# PWR.net
KiCad netlist of a schematic drawn in Altium Designer
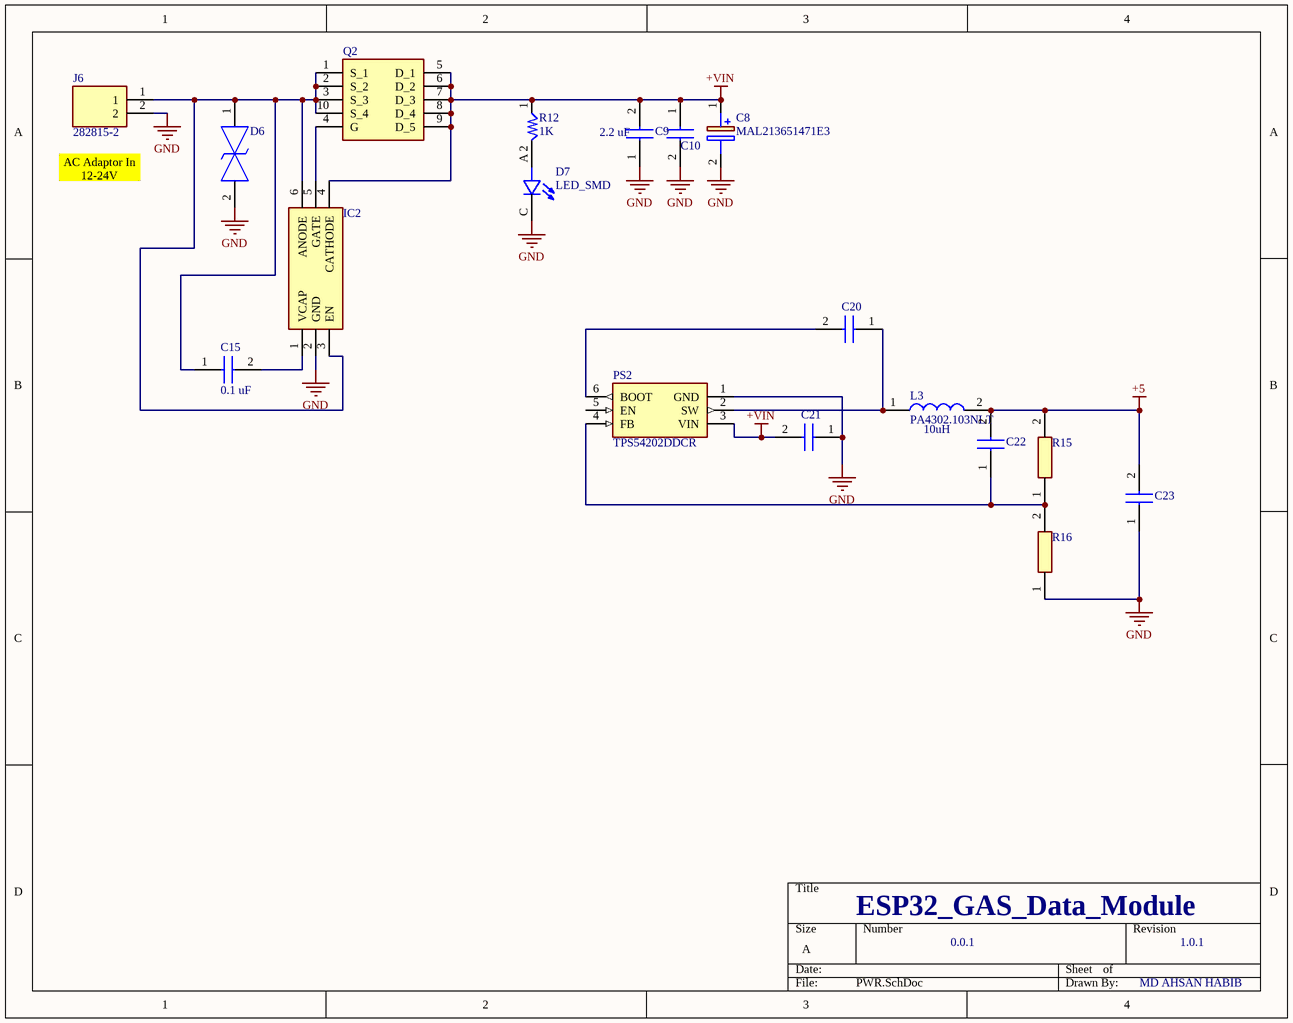
[diagram p0: PWR.SchDoc]

(export (version "E")
  (design (tool "Eeschema 10.0.6"))
  (components
    (comp (ref "C8")
      (value "MAL213651471E3")
      (footprint "CAPPRD500W60D1300H2700")
      (description "Capacitor Polarised")
      (fields (field (name "MOUSER PART NUMBER") "594-2222-136-51471"))
      (libsource (lib "Valve_Controller_Lib") (part "MAL213651471E3"))
    )
    (comp (ref "C9")
      (value "2.2 uF")
      (footprint "CAP0603")
      (description "Capacitor")
      (fields
        (field (name "MANUFACTURER_PART_NUMBER") "CC0603KRX7R9BB104")
        (field (name "MOUSER PART NUMBER") "603-CC603KRX7R9BB104")
      )
      (libsource (lib "Valve_Controller_Lib") (part "CC0603KRX7R9BB104"))
    )
    (comp (ref "C10")
      (value "C5750X5R1H106K230KA")
      (footprint "C5750_Commercial")
      (description "Capacitor")
      (fields (field (name "MOUSER PART NUMBER") "810-C5750X5R1H106K"))
      (libsource (lib "Valve_Controller_Lib") (part "C5750X5R1H106K230KA"))
    )
    (comp (ref "C15")
      (value "0.1 uF")
      (footprint "CAP0603")
      (description "Capacitor")
      (fields
        (field (name "MANUFACTURER_PART_NUMBER") "CC0603KRX7R9BB104")
        (field (name "MOUSER PART NUMBER") "603-CC603KRX7R9BB104")
      )
      (libsource (lib "Valve_Controller_Lib") (part "CC0603KRX7R9BB104"))
    )
    (comp (ref "C20")
      (value "C0805C104M5RAC-TU")
      (footprint "CAPC2012X88N")
      (description "Capacitor")
      (libsource (lib "Valve_Controller_Lib") (part "C0805C104M5RAC-TU"))
    )
    (comp (ref "C21")
      (value "C5750X5R1H106K230KA")
      (footprint "CAP0603")
      (description "Capacitor")
      (fields (field (name "MOUSER PART NUMBER") "810-C5750X5R1H106K"))
      (libsource (lib "Valve_Controller_Lib") (part "C5750X5R1H106K230KA"))
    )
    (comp (ref "C22")
      (value "CGA1A2C0G1E820J030BA")
      (footprint "CAP0603")
      (description "Capacitor")
      (libsource (lib "*") (part "CGA1A2C0G1E820J030BA"))
    )
    (comp (ref "C23")
      (value "GRM32ER61C476KE15L")
      (footprint "CAPC3225X270N")
      (description "Capacitor")
      (fields (field (name "MOUSER PART NUMBER") "81-GRM32ER61C476KE5L"))
      (libsource (lib "Valve_Controller_Lib") (part "GRM32ER61C476KE15L"))
    )
    (comp (ref "D6")
      (value "SMBJ24CA-13-F")
      (footprint "SamacSys:DIONM5336X250N")
      (description "TVS Diode (Bi-directional)")
      (fields (field (name "MOUSER PART NUMBER") "621-SMBJ24CA-13-F"))
      (libsource (lib "*") (part "SMBJ24CA-13-F"))
    )
    (comp (ref "D7")
      (value "LED_SMD")
      (footprint "LEDSC125X200X90-2N")
      (description "Red 633nm LED Indication - Discrete 2.1V 0805 (2012 Metric)")
      (fields (field (name "MF") "Dialight") (field (name "MP") "599-0110-007F"))
      (libsource (lib "Valve_Controller_Lib") (part "5990110007F"))
    )
    (comp (ref "IC2")
      (value "LM74700QDBVTQ1")
      (footprint "SamacSys:SOT95P280X145-6N")
      (description "Integrated Circuit")
      (fields (field (name "MANUFACTURER_PART_NUMBER") "LM74700-Q1MKX-1/NOPB"))
      (libsource (lib "*") (part "LM74700-Q1MKX-1_NOPB"))
    )
    (comp (ref "J6")
      (value "282815-2")
      (footprint "SamacSys:SHDRRA2W102P0X508_1X2_1016X1200X850P")
      (description "Connector")
      (fields (field (name "MOUSER PART NUMBER") "571-282815-2"))
      (libsource (lib "*") (part "282815-2"))
    )
    (comp (ref "L3")
      (value "PA4302.103NLT")
      (footprint "SamacSys:PA4302103NLT")
      (description "Inductor")
      (fields (field (name "MOUSER PART NUMBER") "673-PA4302.103NLT"))
      (libsource (lib "*") (part "PA4302.103NLT"))
    )
    (comp (ref "PS2")
      (value "TPS54202DDCR")
      (footprint "SOT95P280X110-6N")
      (description "Power Supply")
      (fields (field (name "MOUSER PART NUMBER") "595-TPS54202DDCR"))
      (libsource (lib "Valve_Controller_Lib") (part "TPS54202DDCR"))
    )
    (comp (ref "Q2")
      (value "BSC014N06NSATMA1")
      (footprint "BSC010N04LS6ATMA1")
      (description "MOSFET (N-Channel)")
      (fields (field (name "MOUSER PART NUMBER") "726-BSC014N06NSATMA1"))
      (libsource (lib "Valve_Controller_Lib") (part "BSC014N06NSATMA1"))
    )
    (comp (ref "R12")
      (value "1K")
      (footprint "RES0603")
      (description "Resistor")
      (fields (field (name "MANUFACTURER_PART_NUMBER") "0603WAF1001T5E"))
      (libsource (lib "Valve_Controller_Lib") (part "RES"))
    )
    (comp (ref "R15")
      (value "CRCW0402100KFKEDHP")
      (footprint "RES0603")
      (description "Resistor")
      (fields (field (name "MOUSER PART NUMBER") "71-CRCW0402100KFKEDH"))
      (libsource (lib "Valve_Controller_Lib") (part "CRCW0402100KFKEDHP"))
    )
    (comp (ref "R16")
      (value "CRCW040213K7FKEDHP")
      (footprint "RES0603")
      (description "Resistor")
      (libsource (lib "*") (part "CRCW040213K7FKEDHP"))
    )
  )
  (nets
    (net (code "1") (name "+5") (class "Default")
      (node (ref "C22") (pin "2") (pinfunction "2_2") (pintype "passive"))
      (node (ref "C23") (pin "2") (pinfunction "2_2") (pintype "passive"))
      (node (ref "L3") (pin "2") (pinfunction "2_2") (pintype "passive"))
      (node (ref "R15") (pin "2") (pinfunction "2_2") (pintype "passive"))
    )
    (net (code "2") (name "+VIN") (class "Default")
      (node (ref "C10") (pin "1") (pinfunction "1_1") (pintype "passive"))
      (node (ref "C21") (pin "2") (pinfunction "2_2") (pintype "passive"))
      (node (ref "C8") (pin "1") (pinfunction "+_1") (pintype "passive"))
      (node (ref "C9") (pin "2") (pinfunction "2_2") (pintype "passive"))
      (node (ref "IC2") (pin "4") (pinfunction "CATHODE_4") (pintype "passive"))
      (node (ref "PS2") (pin "3") (pinfunction "VIN_3") (pintype "power_in"))
      (node (ref "Q2") (pin "5") (pinfunction "D_1_5") (pintype "passive"))
      (node (ref "Q2") (pin "6") (pinfunction "D_2_6") (pintype "passive"))
      (node (ref "Q2") (pin "7") (pinfunction "D_3_7") (pintype "passive"))
      (node (ref "Q2") (pin "8") (pinfunction "D_4_8") (pintype "passive"))
      (node (ref "Q2") (pin "9") (pinfunction "D_5_9") (pintype "passive"))
      (node (ref "R12") (pin "1") (pinfunction "1_1") (pintype "passive"))
    )
    (net (code "3") (name "GND") (class "Default")
      (node (ref "C10") (pin "2") (pinfunction "2_2") (pintype "passive"))
      (node (ref "C21") (pin "1") (pinfunction "1_1") (pintype "passive"))
      (node (ref "C23") (pin "1") (pinfunction "1_1") (pintype "passive"))
      (node (ref "C8") (pin "2") (pinfunction "-_2") (pintype "passive"))
      (node (ref "C9") (pin "1") (pinfunction "1_1") (pintype "passive"))
      (node (ref "D6") (pin "2") (pinfunction "2_2") (pintype "passive"))
      (node (ref "D7") (pin "C") (pinfunction "C_C") (pintype "passive"))
      (node (ref "IC2") (pin "2") (pinfunction "GND_2") (pintype "passive"))
      (node (ref "J6") (pin "2") (pinfunction "2_2") (pintype "passive"))
      (node (ref "PS2") (pin "1") (pinfunction "GND_1") (pintype "power_in"))
      (node (ref "R16") (pin "1") (pinfunction "1_1") (pintype "passive"))
    )
    (net (code "4") (name "Net-(D7-PadA)") (class "Default")
      (node (ref "D7") (pin "A") (pinfunction "A_A") (pintype "passive"))
      (node (ref "R12") (pin "2") (pinfunction "2_2") (pintype "passive"))
    )
    (net (code "5") (name "Net-(IC2-ANODE)") (class "Default")
      (node (ref "C15") (pin "1") (pinfunction "1_1") (pintype "passive"))
      (node (ref "D6") (pin "1") (pinfunction "1_1") (pintype "passive"))
      (node (ref "IC2") (pin "3") (pinfunction "EN_3") (pintype "passive"))
      (node (ref "IC2") (pin "6") (pinfunction "ANODE_6") (pintype "passive"))
      (node (ref "J6") (pin "1") (pinfunction "1_1") (pintype "passive"))
      (node (ref "Q2") (pin "1") (pinfunction "S_1_1") (pintype "passive"))
      (node (ref "Q2") (pin "10") (pinfunction "S_4_10") (pintype "passive"))
      (node (ref "Q2") (pin "2") (pinfunction "S_2_2") (pintype "passive"))
      (node (ref "Q2") (pin "3") (pinfunction "S_3_3") (pintype "passive"))
    )
    (net (code "6") (name "Net-(IC2-GATE)") (class "Default")
      (node (ref "IC2") (pin "5") (pinfunction "GATE_5") (pintype "passive"))
      (node (ref "Q2") (pin "4") (pinfunction "G_4") (pintype "passive"))
    )
    (net (code "7") (name "Net-(IC2-VCAP)") (class "Default")
      (node (ref "C15") (pin "2") (pinfunction "2_2") (pintype "passive"))
      (node (ref "IC2") (pin "1") (pinfunction "VCAP_1") (pintype "passive"))
    )
    (net (code "8") (name "Net-(PS2-BOOT)") (class "Default")
      (node (ref "C20") (pin "2") (pinfunction "2_2") (pintype "passive"))
      (node (ref "PS2") (pin "6") (pinfunction "BOOT_6") (pintype "output"))
    )
    (net (code "9") (name "Net-(PS2-FB)") (class "Default")
      (node (ref "C22") (pin "1") (pinfunction "1_1") (pintype "passive"))
      (node (ref "PS2") (pin "4") (pinfunction "FB_4") (pintype "input"))
      (node (ref "R15") (pin "1") (pinfunction "1_1") (pintype "passive"))
      (node (ref "R16") (pin "2") (pinfunction "2_2") (pintype "passive"))
    )
    (net (code "10") (name "Net-(PS2-SW)") (class "Default")
      (node (ref "C20") (pin "1") (pinfunction "1_1") (pintype "passive"))
      (node (ref "L3") (pin "1") (pinfunction "1_1") (pintype "passive"))
      (node (ref "PS2") (pin "2") (pinfunction "SW_2") (pintype "output"))
    )
    (net (code "11") (name "unconnected-(PS2-EN-Pad5)") (class "Default")
      (node (ref "PS2") (pin "5") (pinfunction "EN_5") (pintype "input"))
    )
  )
)
